# single_4in5_flex_5led.net
KiCad netlist of a schematic drawn in EAGLE
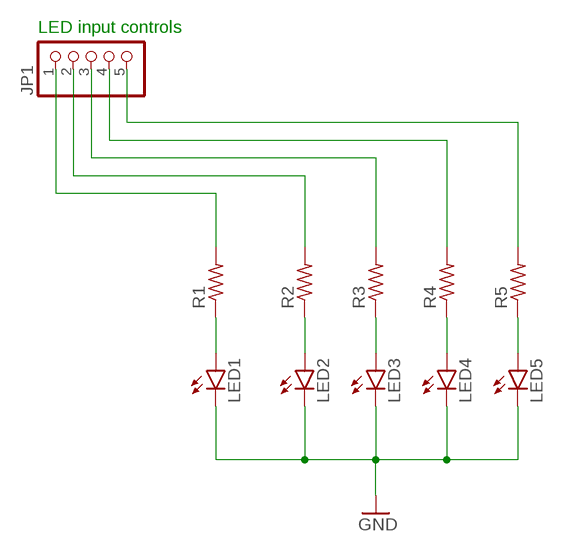
[diagram p0: schematic, sheet 1]

(export (version "E")
  (design (tool "Eeschema 10.0.6"))
  (components
    (comp (ref "JP1")
      (value "PINHD-1X5")
      (footprint "eagle-import:1X05")
      (libsource (lib "eagle-import") (part "PINHD-1X5"))
    )
    (comp (ref "LED1")
      (value "LED5MM")
      (footprint "eagle-import:LED5MM")
      (libsource (lib "eagle-import") (part "LED5MM"))
    )
    (comp (ref "LED2")
      (value "LED5MM")
      (footprint "eagle-import:LED5MM")
      (libsource (lib "eagle-import") (part "LED5MM"))
    )
    (comp (ref "LED3")
      (value "LED5MM")
      (footprint "eagle-import:LED5MM")
      (libsource (lib "eagle-import") (part "LED5MM"))
    )
    (comp (ref "LED4")
      (value "LED5MM")
      (footprint "eagle-import:LED5MM")
      (libsource (lib "eagle-import") (part "LED5MM"))
    )
    (comp (ref "LED5")
      (value "LED5MM")
      (footprint "eagle-import:LED5MM")
      (libsource (lib "eagle-import") (part "LED5MM"))
    )
    (comp (ref "R1")
      (value "R-US_0207/7")
      (footprint "eagle-import:0207_7")
      (libsource (lib "eagle-import") (part "R-US_0207/7"))
    )
    (comp (ref "R2")
      (value "R-US_0207/7")
      (footprint "eagle-import:0207_7")
      (libsource (lib "eagle-import") (part "R-US_0207/7"))
    )
    (comp (ref "R3")
      (value "R-US_0207/7")
      (footprint "eagle-import:0207_7")
      (libsource (lib "eagle-import") (part "R-US_0207/7"))
    )
    (comp (ref "R4")
      (value "R-US_0207/7")
      (footprint "eagle-import:0207_7")
      (libsource (lib "eagle-import") (part "R-US_0207/7"))
    )
    (comp (ref "R5")
      (value "R-US_0207/7")
      (footprint "eagle-import:0207_7")
      (libsource (lib "eagle-import") (part "R-US_0207/7"))
    )
  )
  (nets
    (net (code "1") (name "GND") (class "Default")
      (node (ref "LED1") (pin "K") (pinfunction "C_K") (pintype "passive"))
      (node (ref "LED2") (pin "K") (pinfunction "C_K") (pintype "passive"))
      (node (ref "LED3") (pin "K") (pinfunction "C_K") (pintype "passive"))
      (node (ref "LED4") (pin "K") (pinfunction "C_K") (pintype "passive"))
      (node (ref "LED5") (pin "K") (pinfunction "C_K") (pintype "passive"))
    )
    (net (code "2") (name "Net-(JP1-Pad1)") (class "Default")
      (node (ref "JP1") (pin "1") (pinfunction "1_1") (pintype "passive"))
      (node (ref "R1") (pin "2") (pinfunction "2_2") (pintype "passive"))
    )
    (net (code "3") (name "Net-(JP1-Pad2)") (class "Default")
      (node (ref "JP1") (pin "2") (pinfunction "2_2") (pintype "passive"))
      (node (ref "R2") (pin "2") (pinfunction "2_2") (pintype "passive"))
    )
    (net (code "4") (name "Net-(JP1-Pad3)") (class "Default")
      (node (ref "JP1") (pin "3") (pinfunction "3_3") (pintype "passive"))
      (node (ref "R3") (pin "2") (pinfunction "2_2") (pintype "passive"))
    )
    (net (code "5") (name "Net-(JP1-Pad4)") (class "Default")
      (node (ref "JP1") (pin "4") (pinfunction "4_4") (pintype "passive"))
      (node (ref "R4") (pin "2") (pinfunction "2_2") (pintype "passive"))
    )
    (net (code "6") (name "Net-(JP1-Pad5)") (class "Default")
      (node (ref "JP1") (pin "5") (pinfunction "5_5") (pintype "passive"))
      (node (ref "R5") (pin "2") (pinfunction "2_2") (pintype "passive"))
    )
    (net (code "7") (name "Net-(LED1-PadA)") (class "Default")
      (node (ref "LED1") (pin "A") (pinfunction "A_A") (pintype "passive"))
      (node (ref "R1") (pin "1") (pinfunction "1_1") (pintype "passive"))
    )
    (net (code "8") (name "Net-(LED2-PadA)") (class "Default")
      (node (ref "LED2") (pin "A") (pinfunction "A_A") (pintype "passive"))
      (node (ref "R2") (pin "1") (pinfunction "1_1") (pintype "passive"))
    )
    (net (code "9") (name "Net-(LED3-PadA)") (class "Default")
      (node (ref "LED3") (pin "A") (pinfunction "A_A") (pintype "passive"))
      (node (ref "R3") (pin "1") (pinfunction "1_1") (pintype "passive"))
    )
    (net (code "10") (name "Net-(LED4-PadA)") (class "Default")
      (node (ref "LED4") (pin "A") (pinfunction "A_A") (pintype "passive"))
      (node (ref "R4") (pin "1") (pinfunction "1_1") (pintype "passive"))
    )
    (net (code "11") (name "Net-(LED5-PadA)") (class "Default")
      (node (ref "LED5") (pin "A") (pinfunction "A_A") (pintype "passive"))
      (node (ref "R5") (pin "1") (pinfunction "1_1") (pintype "passive"))
    )
  )
)
